# lcdshield.net
KiCad netlist of a schematic drawn in EAGLE
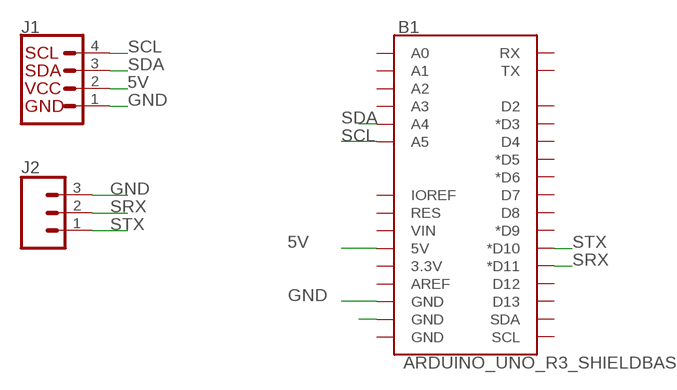
[diagram p0: schematic, sheet 1]

(export (version "E")
  (design (tool "Eeschema 10.0.6"))
  (components
    (comp (ref "B1")
      (value "ARDUINO_UNO_R3_SHIELDBASIC")
      (footprint "eagle-import:UNO_R3_SHIELD")
      (libsource (lib "eagle-import") (part "ARDUINO_UNO_R3_SHIELDBASIC"))
    )
    (comp (ref "J1")
      (value "I2C_STANDARD")
      (footprint "eagle-import:1X04")
      (libsource (lib "eagle-import") (part "I2C_STANDARD"))
    )
    (comp (ref "J2")
      (value "CONN_03")
      (footprint "eagle-import:1X03")
      (libsource (lib "eagle-import") (part "CONN_03"))
    )
  )
  (nets
    (net (code "1") (name "/5V") (class "Default")
      (node (ref "B1") (pin "5V") (pinfunction "5V_5V") (pintype "bidirectional"))
      (node (ref "J1") (pin "2") (pinfunction "2_2") (pintype "power_in"))
    )
    (net (code "2") (name "/GND") (class "Default")
      (node (ref "B1") (pin "GND@1") (pinfunction "GND_GND@1") (pintype "bidirectional"))
      (node (ref "B1") (pin "GND@2") (pinfunction "GND_GND@2") (pintype "bidirectional"))
      (node (ref "J1") (pin "1") (pinfunction "1_1") (pintype "power_in"))
      (node (ref "J2") (pin "3") (pinfunction "3_3") (pintype "passive"))
    )
    (net (code "3") (name "/SCL") (class "Default")
      (node (ref "B1") (pin "A5") (pinfunction "A5_A5") (pintype "bidirectional"))
      (node (ref "J1") (pin "4") (pinfunction "4_4") (pintype "passive"))
    )
    (net (code "4") (name "/SDA") (class "Default")
      (node (ref "B1") (pin "A4") (pinfunction "A4_A4") (pintype "bidirectional"))
      (node (ref "J1") (pin "3") (pinfunction "3_3") (pintype "passive"))
    )
    (net (code "5") (name "/SRX") (class "Default")
      (node (ref "B1") (pin "D11") (pinfunction "*D11_D11") (pintype "bidirectional"))
      (node (ref "J2") (pin "2") (pinfunction "2_2") (pintype "passive"))
    )
    (net (code "6") (name "/STX") (class "Default")
      (node (ref "B1") (pin "D10") (pinfunction "*D10_D10") (pintype "bidirectional"))
      (node (ref "J2") (pin "1") (pinfunction "1_1") (pintype "passive"))
    )
    (net (code "7") (name "unconnected-(B1-*D3-PadD3)") (class "Default")
      (node (ref "B1") (pin "D3") (pinfunction "*D3_D3") (pintype "bidirectional"))
    )
    (net (code "8") (name "unconnected-(B1-*D5-PadD5)") (class "Default")
      (node (ref "B1") (pin "D5") (pinfunction "*D5_D5") (pintype "bidirectional"))
    )
    (net (code "9") (name "unconnected-(B1-*D6-PadD6)") (class "Default")
      (node (ref "B1") (pin "D6") (pinfunction "*D6_D6") (pintype "bidirectional"))
    )
    (net (code "10") (name "unconnected-(B1-*D9-PadD9)") (class "Default")
      (node (ref "B1") (pin "D9") (pinfunction "*D9_D9") (pintype "bidirectional"))
    )
    (net (code "11") (name "unconnected-(B1-GND-PadGND@0)") (class "Default")
      (node (ref "B1") (pin "GND@0") (pinfunction "GND_GND@0") (pintype "bidirectional"))
    )
    (net (code "12") (name "unconnected-(B1-Pad3.3V)") (class "Default")
      (node (ref "B1") (pin "3.3V") (pinfunction "3.3V_3.3V") (pintype "bidirectional"))
    )
    (net (code "13") (name "unconnected-(B1-PadA0)") (class "Default")
      (node (ref "B1") (pin "A0") (pinfunction "A0_A0") (pintype "bidirectional"))
    )
    (net (code "14") (name "unconnected-(B1-PadA1)") (class "Default")
      (node (ref "B1") (pin "A1") (pinfunction "A1_A1") (pintype "bidirectional"))
    )
    (net (code "15") (name "unconnected-(B1-PadA2)") (class "Default")
      (node (ref "B1") (pin "A2") (pinfunction "A2_A2") (pintype "bidirectional"))
    )
    (net (code "16") (name "unconnected-(B1-PadA3)") (class "Default")
      (node (ref "B1") (pin "A3") (pinfunction "A3_A3") (pintype "bidirectional"))
    )
    (net (code "17") (name "unconnected-(B1-PadAREF)") (class "Default")
      (node (ref "B1") (pin "AREF") (pinfunction "AREF_AREF") (pintype "bidirectional"))
    )
    (net (code "18") (name "unconnected-(B1-PadD2)") (class "Default")
      (node (ref "B1") (pin "D2") (pinfunction "D2_D2") (pintype "bidirectional"))
    )
    (net (code "19") (name "unconnected-(B1-PadD4)") (class "Default")
      (node (ref "B1") (pin "D4") (pinfunction "D4_D4") (pintype "bidirectional"))
    )
    (net (code "20") (name "unconnected-(B1-PadD7)") (class "Default")
      (node (ref "B1") (pin "D7") (pinfunction "D7_D7") (pintype "bidirectional"))
    )
    (net (code "21") (name "unconnected-(B1-PadD8)") (class "Default")
      (node (ref "B1") (pin "D8") (pinfunction "D8_D8") (pintype "bidirectional"))
    )
    (net (code "22") (name "unconnected-(B1-PadD12)") (class "Default")
      (node (ref "B1") (pin "D12") (pinfunction "D12_D12") (pintype "bidirectional"))
    )
    (net (code "23") (name "unconnected-(B1-PadD13)") (class "Default")
      (node (ref "B1") (pin "D13") (pinfunction "D13_D13") (pintype "bidirectional"))
    )
    (net (code "24") (name "unconnected-(B1-PadIOREF)") (class "Default")
      (node (ref "B1") (pin "IOREF") (pinfunction "IOREF_IOREF") (pintype "bidirectional"))
    )
    (net (code "25") (name "unconnected-(B1-PadRES)") (class "Default")
      (node (ref "B1") (pin "RES") (pinfunction "RES_RES") (pintype "bidirectional"))
    )
    (net (code "26") (name "unconnected-(B1-PadRX)") (class "Default")
      (node (ref "B1") (pin "RX") (pinfunction "RX_RX") (pintype "bidirectional"))
    )
    (net (code "27") (name "unconnected-(B1-PadSCL)") (class "Default")
      (node (ref "B1") (pin "SCL") (pinfunction "SCL_SCL") (pintype "bidirectional"))
    )
    (net (code "28") (name "unconnected-(B1-PadSDA)") (class "Default")
      (node (ref "B1") (pin "SDA") (pinfunction "SDA_SDA") (pintype "bidirectional"))
    )
    (net (code "29") (name "unconnected-(B1-PadTX)") (class "Default")
      (node (ref "B1") (pin "TX") (pinfunction "TX_TX") (pintype "bidirectional"))
    )
    (net (code "30") (name "unconnected-(B1-PadVIN)") (class "Default")
      (node (ref "B1") (pin "VIN") (pinfunction "VIN_VIN") (pintype "bidirectional"))
    )
  )
)
